# DataConvX13.net
KiCad netlist of a schematic drawn in EAGLE
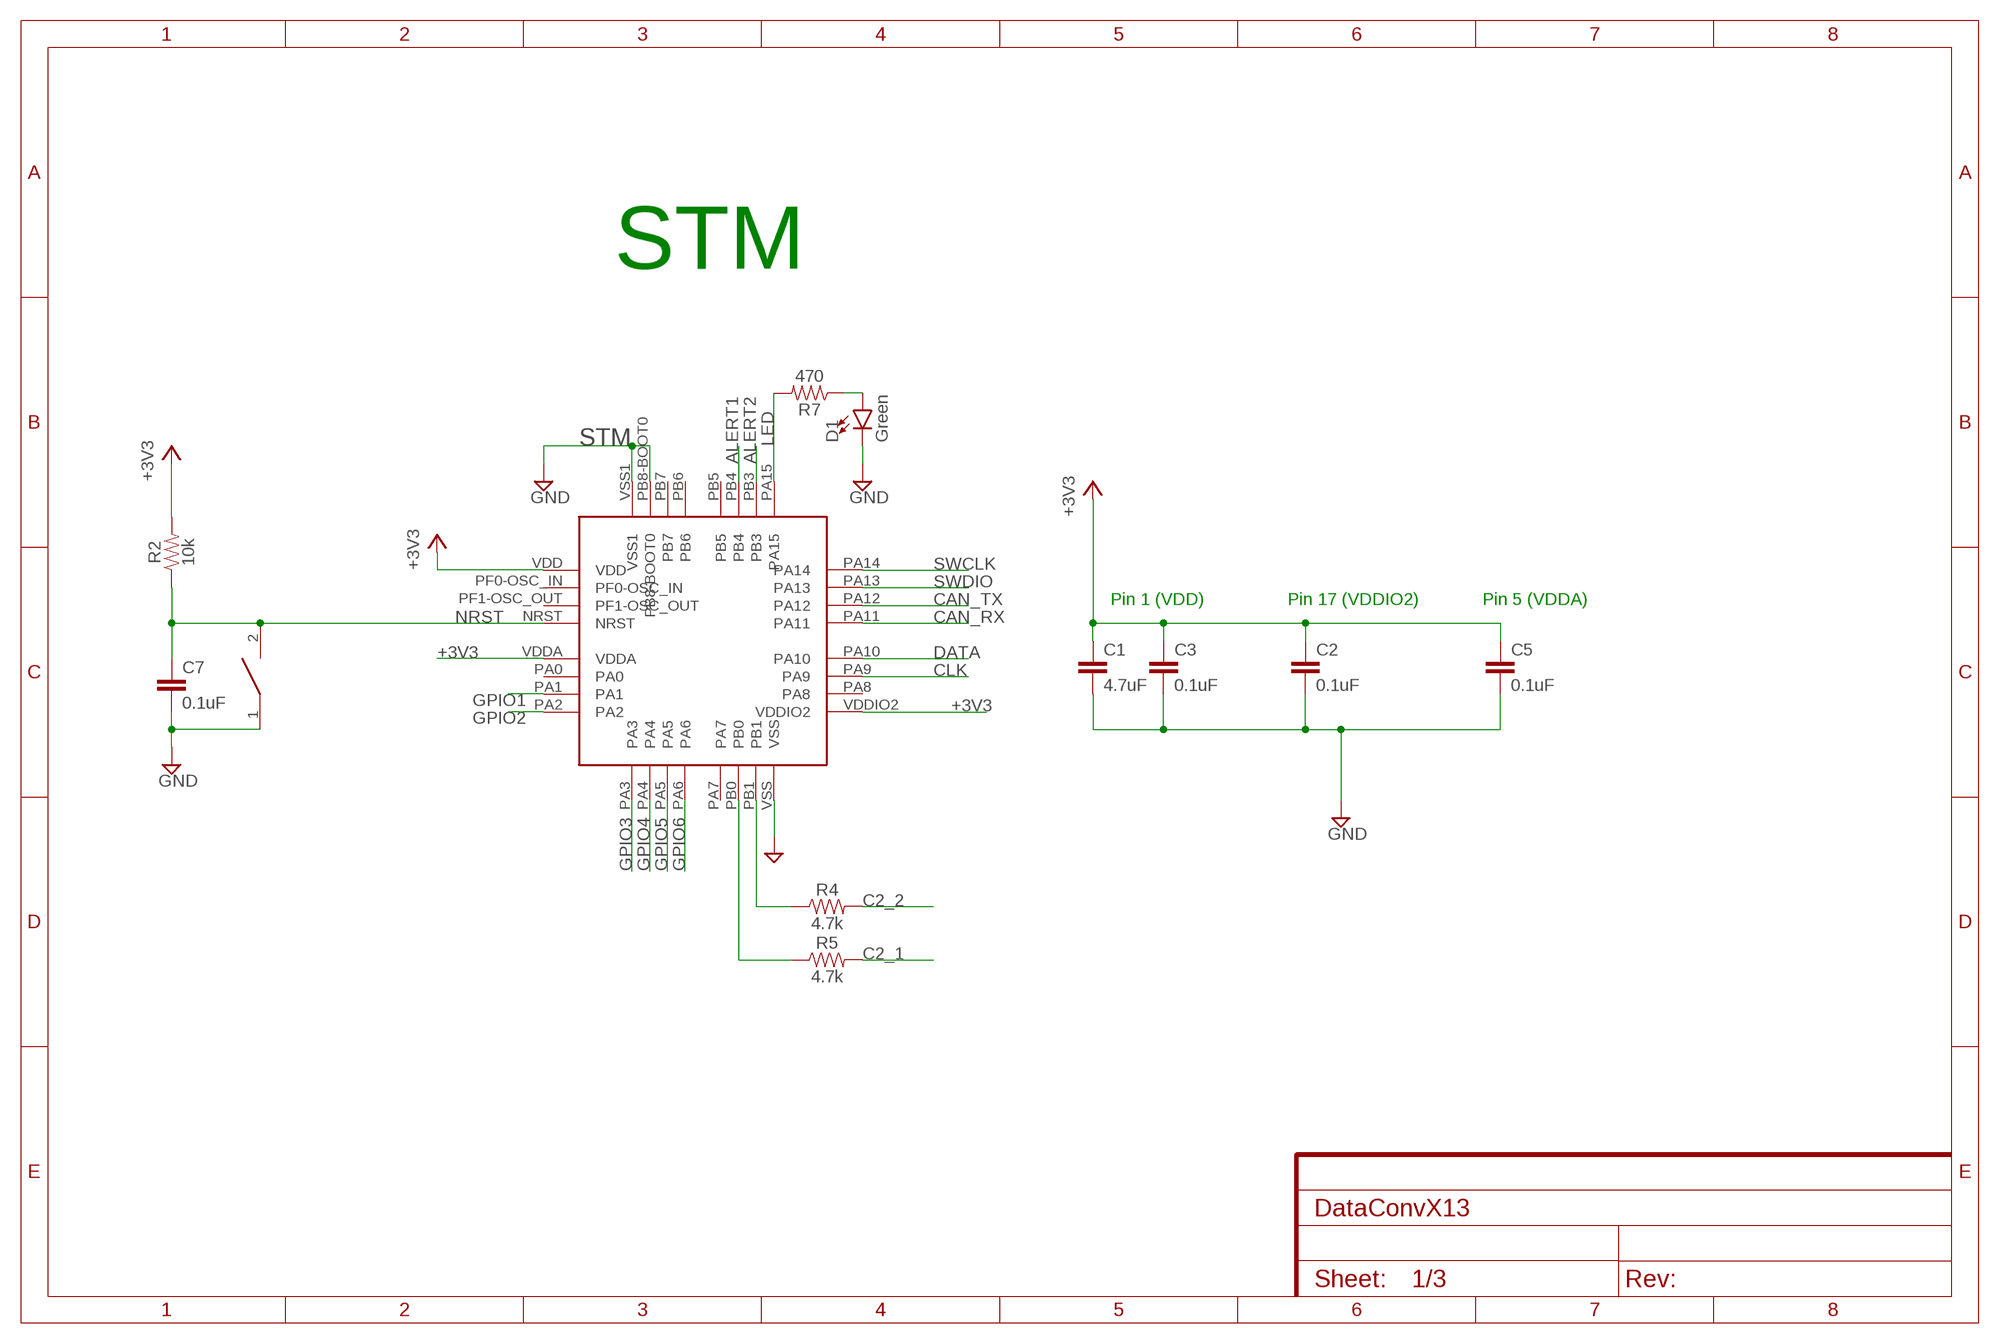
[diagram p0: schematic, sheet 1]
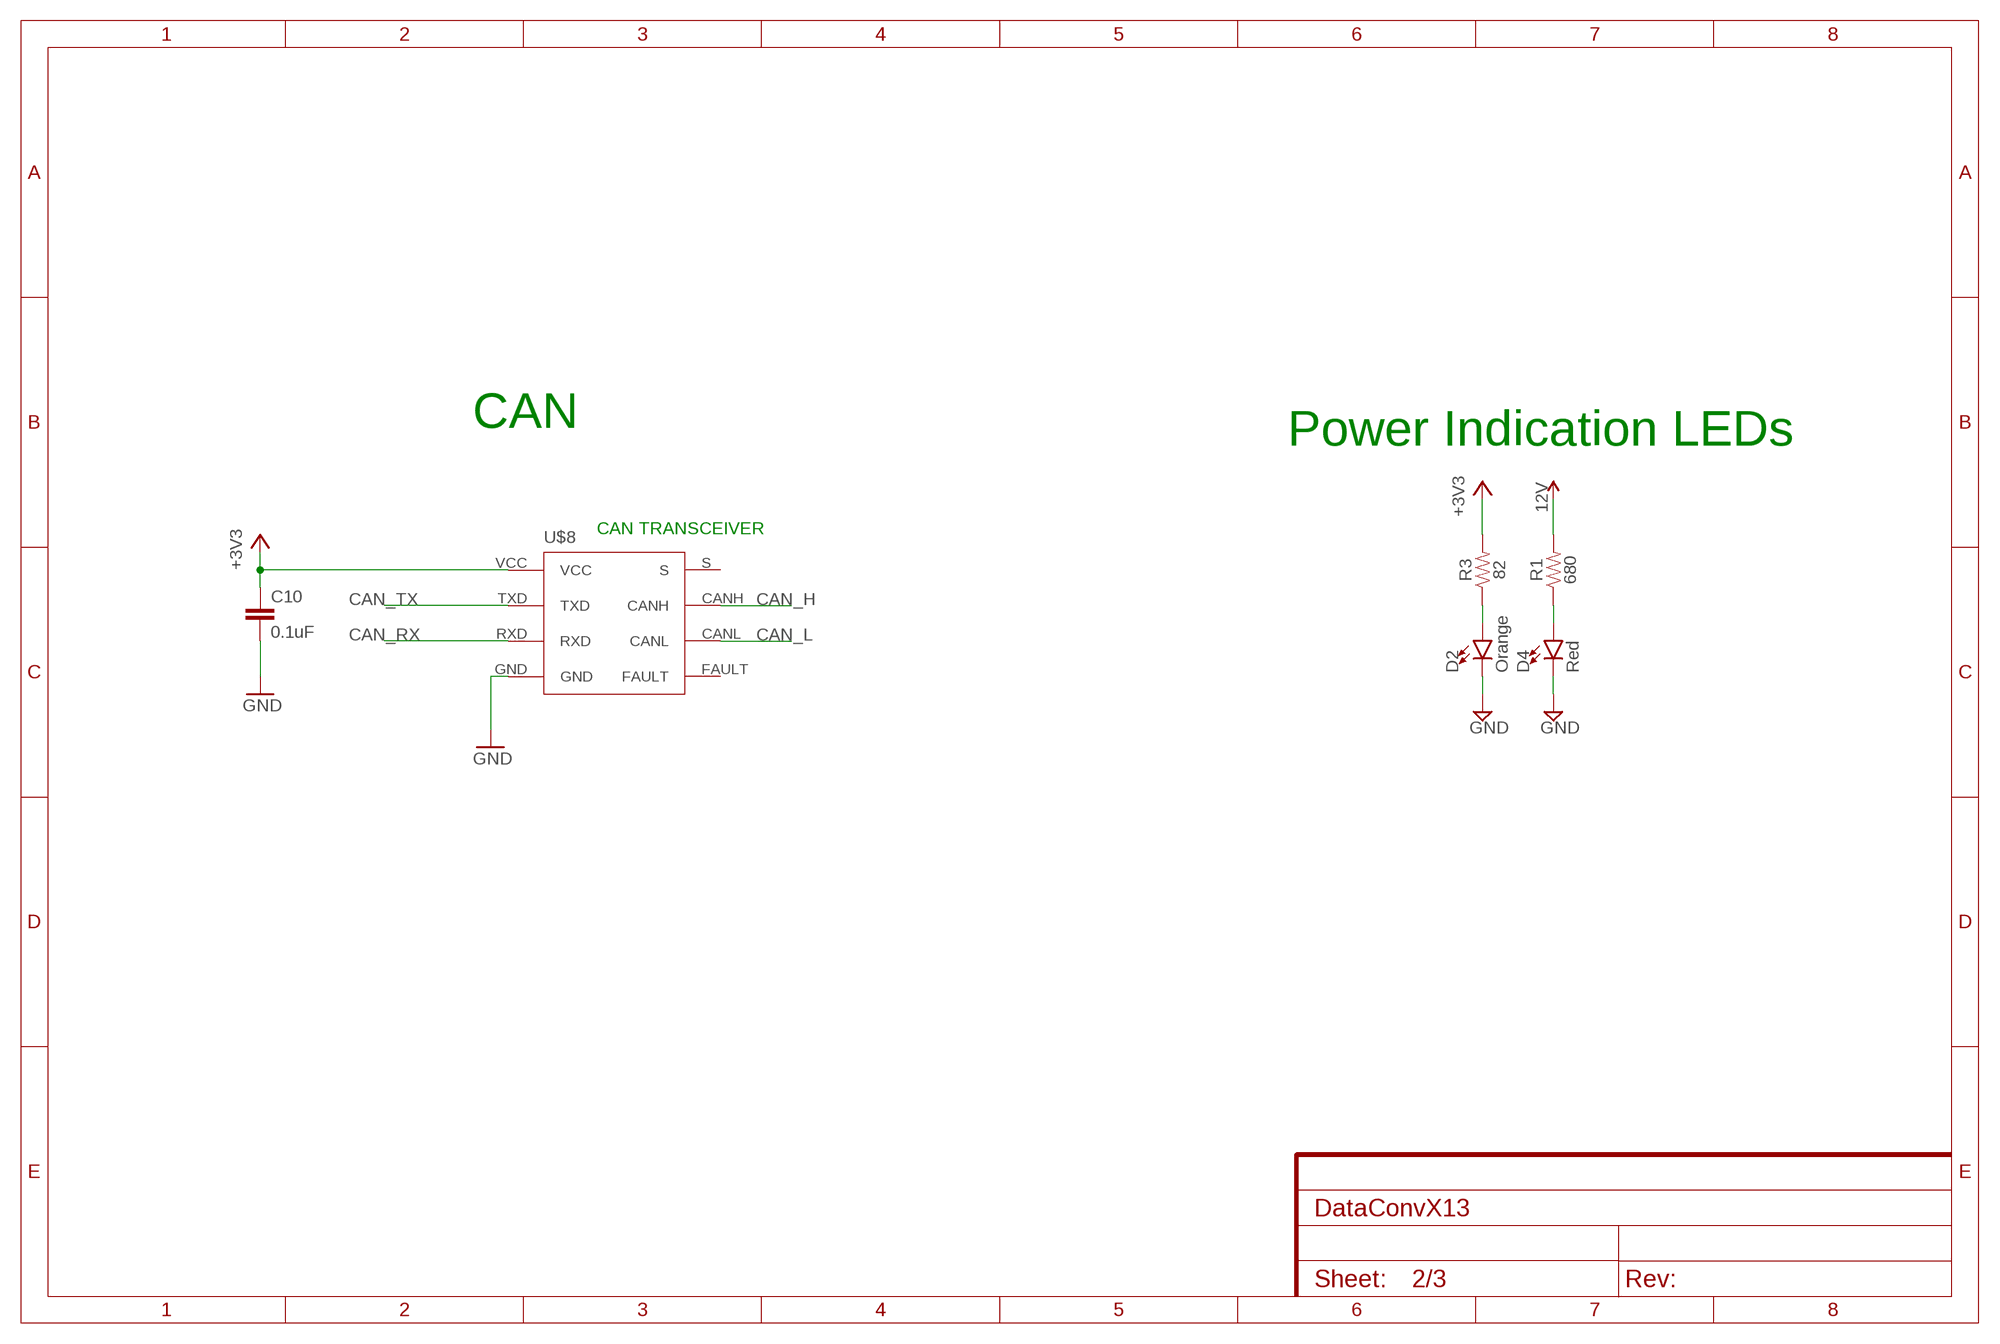
[diagram p1: schematic, sheet 2]
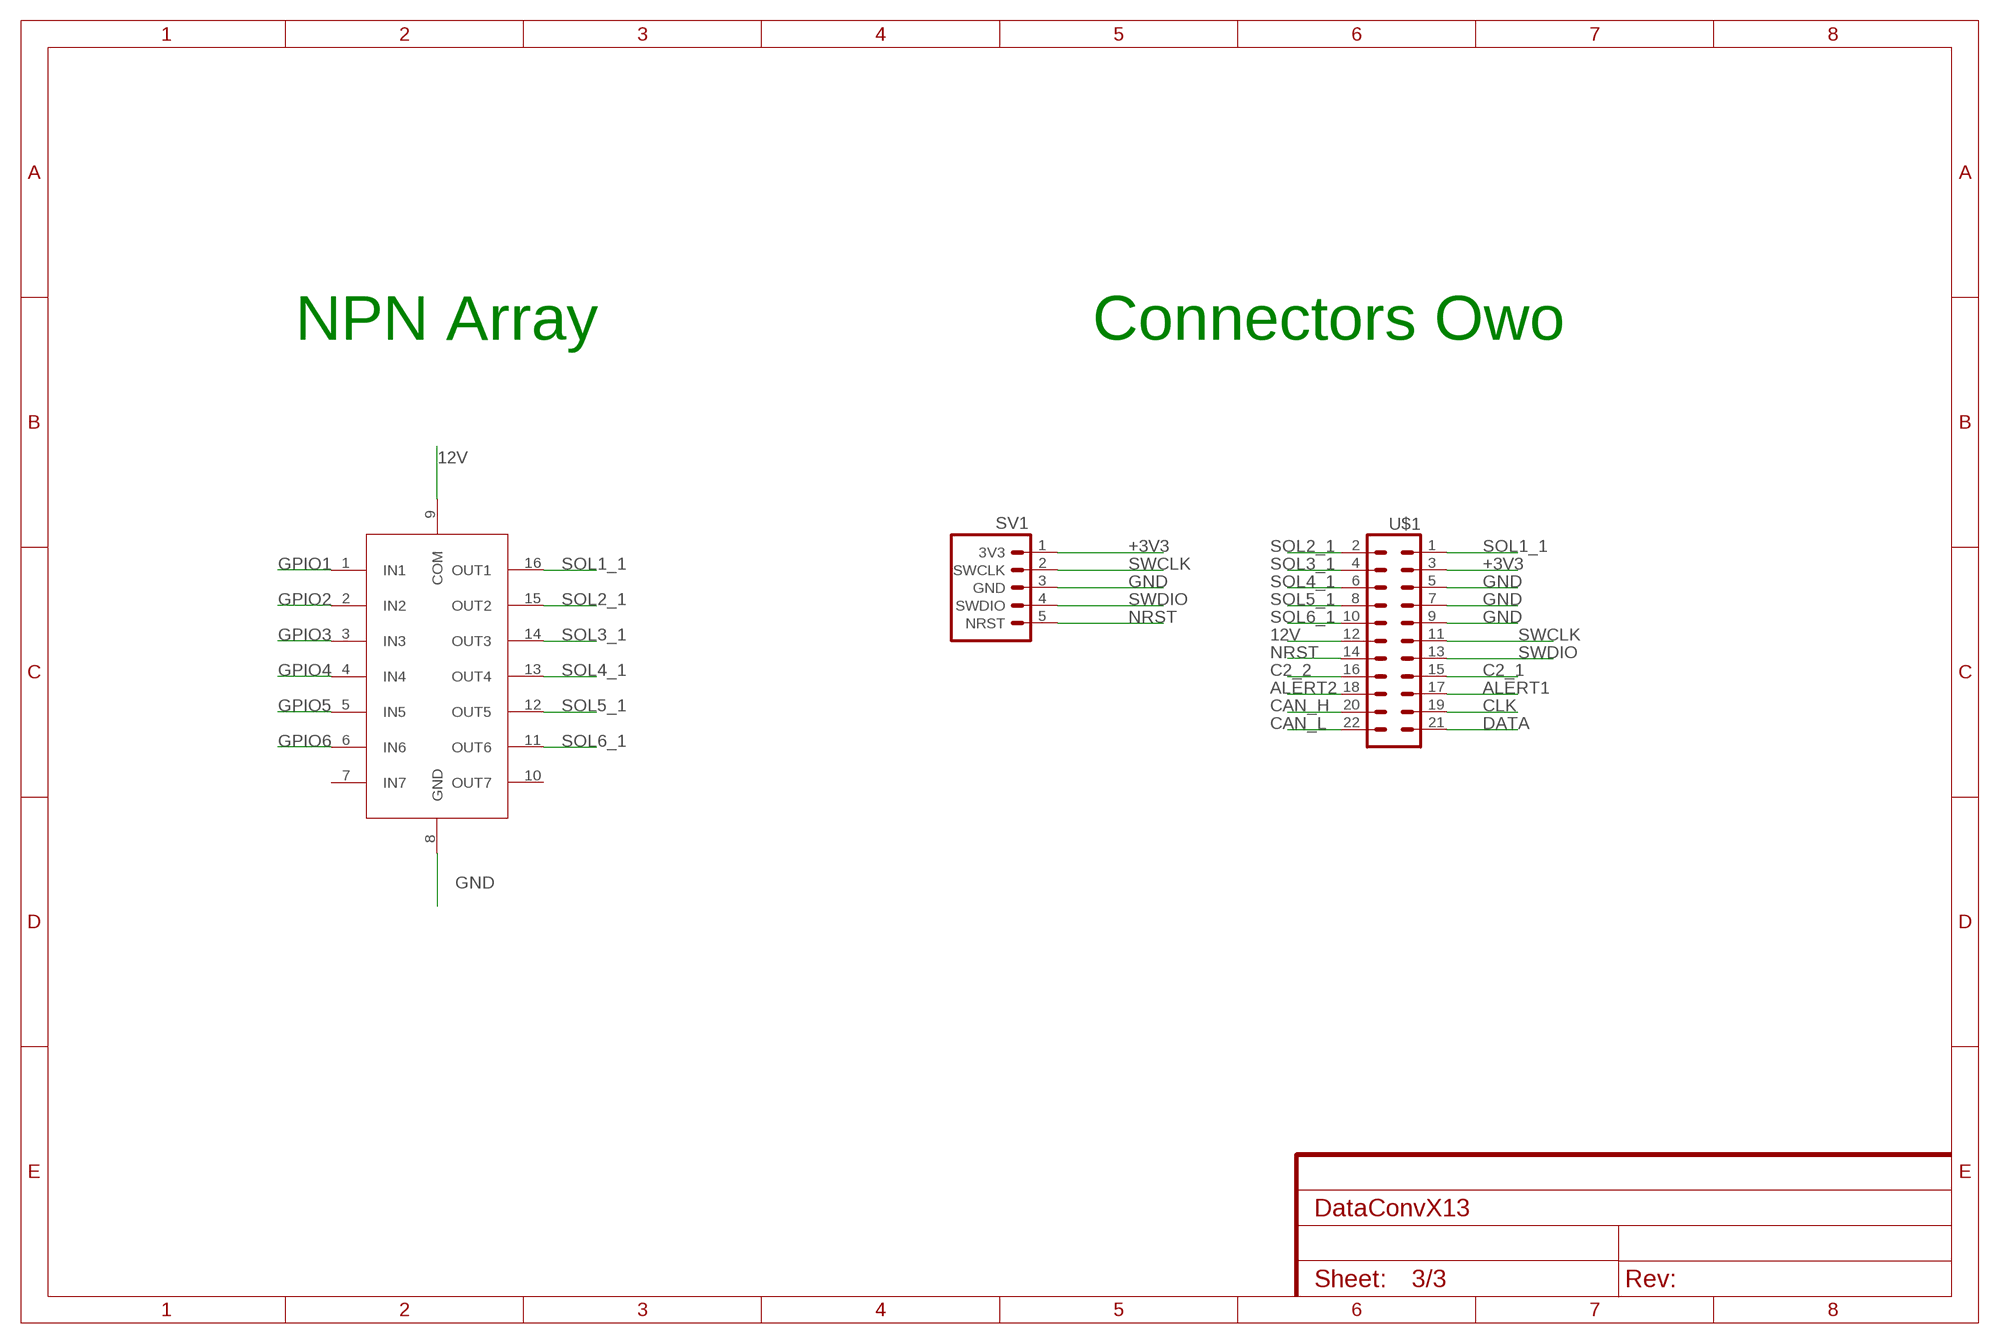
[diagram p2: schematic, sheet 3]

(export (version "E")
  (design (tool "Eeschema 10.0.6"))
  (components
    (comp (ref "C1")
      (value "4.7uF")
      (footprint "eagle-import:0603")
      (libsource (lib "eagle-import") (part "4.7UF0603"))
    )
    (comp (ref "C2")
      (value "0.1uF")
      (footprint "eagle-import:0603")
      (libsource (lib "eagle-import") (part "4.7UF0603"))
    )
    (comp (ref "C3")
      (value "0.1uF")
      (footprint "eagle-import:0603")
      (libsource (lib "eagle-import") (part "4.7UF0603"))
    )
    (comp (ref "C5")
      (value "0.1uF")
      (footprint "eagle-import:0603")
      (libsource (lib "eagle-import") (part "4.7UF0603"))
    )
    (comp (ref "C7")
      (value "0.1uF")
      (footprint "eagle-import:0603")
      (libsource (lib "eagle-import") (part "4.7UF0603"))
    )
    (comp (ref "D1")
      (value "Green")
      (footprint "eagle-import:LED-0603")
      (libsource (lib "eagle-import") (part "LED0603"))
    )
    (comp (ref "R2")
      (value "10k")
      (footprint "eagle-import:0603")
      (libsource (lib "eagle-import") (part "1KOHM-0603-1/10W-1%"))
    )
    (comp (ref "R4")
      (value "4.7k")
      (footprint "eagle-import:0603")
      (libsource (lib "eagle-import") (part "4.7KOHM-0603-1/10W-1%"))
    )
    (comp (ref "R5")
      (value "4.7k")
      (footprint "eagle-import:0603")
      (libsource (lib "eagle-import") (part "4.7KOHM-0603-1/10W-1%"))
    )
    (comp (ref "R7")
      (value "470")
      (footprint "eagle-import:0603")
      (libsource (lib "eagle-import") (part "RESISTOR0603"))
    )
    (comp (ref "RESET")
      (value "DISCRETECOMPONENTS_SWITCH")
      (footprint "eagle-import:DISCRETECOMPONENTS_SW_2512")
      (libsource (lib "eagle-import") (part "DISCRETECOMPONENTS_SWITCH"))
    )
    (comp (ref "STM")
      (value "STM32F042K6T6")
      (footprint "eagle-import:STM32F042K6T6")
      (libsource (lib "eagle-import") (part "STM32F042K6T6"))
    )
    (comp (ref "SV1")
      (value "3V3 -SWCLK-GND-SWDIO- NRST")
      (footprint "eagle-import:1X05")
      (libsource (lib "eagle-import") (part "SWD_CONN"))
    )
    (comp (ref "U$1")
      (value "SOL-TO-BKP")
      (footprint "eagle-import:MMS-111-01-DV")
      (libsource (lib "eagle-import") (part "SOL-TO-BKP"))
    )
    (comp (ref "U1")
      (value "ULN2003V12")
      (footprint "eagle-import:ULN2003V12")
      (fields (field (name "MANUFACTURER") "Diodes Inc."))
      (libsource (lib "eagle-import") (part "ULN2003V12"))
    )
    (comp (ref "C10")
      (value "0.1uF")
      (footprint "eagle-import:0603")
      (libsource (lib "eagle-import") (part "4.7UF0603"))
    )
    (comp (ref "D2")
      (value "Orange")
      (footprint "eagle-import:LED-0603")
      (libsource (lib "eagle-import") (part "LED0603"))
    )
    (comp (ref "D4")
      (value "Red")
      (footprint "eagle-import:LED-0603")
      (libsource (lib "eagle-import") (part "LED0603"))
    )
    (comp (ref "R1")
      (value "680")
      (footprint "eagle-import:0603")
      (libsource (lib "eagle-import") (part "680OHM-0603-1/10W-5%"))
    )
    (comp (ref "R3")
      (value "82")
      (footprint "eagle-import:0603")
      (libsource (lib "eagle-import") (part "82OHM-0603-1/10W-1%"))
    )
    (comp (ref "U$8")
      (value "TCAN337D")
      (footprint "eagle-import:TCAN337D")
      (libsource (lib "eagle-import") (part "TCAN337D"))
    )
  )
  (nets
    (net (code "1") (name "+3V3") (class "Default")
      (node (ref "C1") (pin "1") (pinfunction "1_1") (pintype "passive"))
      (node (ref "C10") (pin "1") (pinfunction "1_1") (pintype "passive"))
      (node (ref "C2") (pin "1") (pinfunction "1_1") (pintype "passive"))
      (node (ref "C3") (pin "1") (pinfunction "1_1") (pintype "passive"))
      (node (ref "C5") (pin "1") (pinfunction "1_1") (pintype "passive"))
      (node (ref "R2") (pin "2") (pinfunction "2_2") (pintype "passive"))
      (node (ref "R3") (pin "2") (pinfunction "2_2") (pintype "passive"))
      (node (ref "STM") (pin "VDD") (pinfunction "VDD_VDD") (pintype "bidirectional"))
      (node (ref "STM") (pin "VDDA") (pinfunction "VDDA_VDDA") (pintype "bidirectional"))
      (node (ref "STM") (pin "VDDIO2") (pinfunction "VDDIO2_VDDIO2") (pintype "bidirectional"))
      (node (ref "SV1") (pin "1") (pinfunction "3V3_1") (pintype "power_in"))
      (node (ref "U$1") (pin "3") (pinfunction "3_3") (pintype "passive"))
      (node (ref "U$8") (pin "VCC") (pinfunction "VCC_VCC") (pintype "bidirectional"))
    )
    (net (code "2") (name "12V") (class "Default")
      (node (ref "R1") (pin "2") (pinfunction "2_2") (pintype "passive"))
      (node (ref "U$1") (pin "12") (pinfunction "12_12") (pintype "passive"))
      (node (ref "U1") (pin "9") (pinfunction "COM_9") (pintype "bidirectional"))
    )
    (net (code "3") (name "ALERT1") (class "Default")
      (node (ref "STM") (pin "PB4") (pinfunction "PB4_PB4") (pintype "bidirectional"))
      (node (ref "U$1") (pin "17") (pinfunction "17_17") (pintype "passive"))
    )
    (net (code "4") (name "ALERT2") (class "Default")
      (node (ref "STM") (pin "PB3") (pinfunction "PB3_PB3") (pintype "bidirectional"))
      (node (ref "U$1") (pin "18") (pinfunction "18_18") (pintype "passive"))
    )
    (net (code "5") (name "C2_1") (class "Default")
      (node (ref "R5") (pin "2") (pinfunction "2_2") (pintype "passive"))
      (node (ref "U$1") (pin "15") (pinfunction "15_15") (pintype "passive"))
    )
    (net (code "6") (name "C2_2") (class "Default")
      (node (ref "R4") (pin "2") (pinfunction "2_2") (pintype "passive"))
      (node (ref "U$1") (pin "16") (pinfunction "16_16") (pintype "passive"))
    )
    (net (code "7") (name "CAN_H") (class "Default")
      (node (ref "U$1") (pin "20") (pinfunction "20_20") (pintype "passive"))
      (node (ref "U$8") (pin "CANH") (pinfunction "CANH_CANH") (pintype "bidirectional"))
    )
    (net (code "8") (name "CAN_L") (class "Default")
      (node (ref "U$1") (pin "22") (pinfunction "22_22") (pintype "passive"))
      (node (ref "U$8") (pin "CANL") (pinfunction "CANL_CANL") (pintype "bidirectional"))
    )
    (net (code "9") (name "CAN_RX") (class "Default")
      (node (ref "STM") (pin "PA11") (pinfunction "PA11_PA11") (pintype "bidirectional"))
      (node (ref "U$8") (pin "RXD") (pinfunction "RXD_RXD") (pintype "bidirectional"))
    )
    (net (code "10") (name "CAN_TX") (class "Default")
      (node (ref "STM") (pin "PA12") (pinfunction "PA12_PA12") (pintype "bidirectional"))
      (node (ref "U$8") (pin "TXD") (pinfunction "TXD_TXD") (pintype "bidirectional"))
    )
    (net (code "11") (name "CLK") (class "Default")
      (node (ref "STM") (pin "PA9") (pinfunction "PA9_PA9") (pintype "bidirectional"))
      (node (ref "U$1") (pin "19") (pinfunction "19_19") (pintype "passive"))
    )
    (net (code "12") (name "DATA") (class "Default")
      (node (ref "STM") (pin "PA10") (pinfunction "PA10_PA10") (pintype "bidirectional"))
      (node (ref "U$1") (pin "21") (pinfunction "21_21") (pintype "passive"))
    )
    (net (code "13") (name "GND") (class "Default")
      (node (ref "C1") (pin "2") (pinfunction "2_2") (pintype "passive"))
      (node (ref "C10") (pin "2") (pinfunction "2_2") (pintype "passive"))
      (node (ref "C2") (pin "2") (pinfunction "2_2") (pintype "passive"))
      (node (ref "C3") (pin "2") (pinfunction "2_2") (pintype "passive"))
      (node (ref "C5") (pin "2") (pinfunction "2_2") (pintype "passive"))
      (node (ref "C7") (pin "2") (pinfunction "2_2") (pintype "passive"))
      (node (ref "D1") (pin "C") (pinfunction "C_C") (pintype "passive"))
      (node (ref "D2") (pin "C") (pinfunction "C_C") (pintype "passive"))
      (node (ref "D4") (pin "C") (pinfunction "C_C") (pintype "passive"))
      (node (ref "RESET") (pin "1") (pinfunction "P$1_1") (pintype "bidirectional"))
      (node (ref "STM") (pin "PB8-BOOT0") (pinfunction "PB8-BOOT0_PB8-BOOT0") (pintype "bidirectional"))
      (node (ref "STM") (pin "VSS") (pinfunction "VSS_VSS") (pintype "bidirectional"))
      (node (ref "STM") (pin "VSS1") (pinfunction "VSS1_VSS1") (pintype "bidirectional"))
      (node (ref "SV1") (pin "3") (pinfunction "GND_3") (pintype "power_in"))
      (node (ref "U$1") (pin "5") (pinfunction "5_5") (pintype "passive"))
      (node (ref "U$1") (pin "7") (pinfunction "7_7") (pintype "passive"))
      (node (ref "U$1") (pin "9") (pinfunction "9_9") (pintype "passive"))
      (node (ref "U$8") (pin "GND") (pinfunction "GND_GND") (pintype "bidirectional"))
      (node (ref "U1") (pin "8") (pinfunction "GND_8") (pintype "bidirectional"))
    )
    (net (code "14") (name "GPIO1") (class "Default")
      (node (ref "STM") (pin "PA1") (pinfunction "PA1_PA1") (pintype "bidirectional"))
      (node (ref "U1") (pin "1") (pinfunction "IN1_1") (pintype "bidirectional"))
    )
    (net (code "15") (name "GPIO2") (class "Default")
      (node (ref "STM") (pin "PA2") (pinfunction "PA2_PA2") (pintype "bidirectional"))
      (node (ref "U1") (pin "2") (pinfunction "IN2_2") (pintype "bidirectional"))
    )
    (net (code "16") (name "GPIO3") (class "Default")
      (node (ref "STM") (pin "PA3") (pinfunction "PA3_PA3") (pintype "bidirectional"))
      (node (ref "U1") (pin "3") (pinfunction "IN3_3") (pintype "bidirectional"))
    )
    (net (code "17") (name "GPIO4") (class "Default")
      (node (ref "STM") (pin "PA4") (pinfunction "PA4_PA4") (pintype "bidirectional"))
      (node (ref "U1") (pin "4") (pinfunction "IN4_4") (pintype "bidirectional"))
    )
    (net (code "18") (name "GPIO5") (class "Default")
      (node (ref "STM") (pin "PA5") (pinfunction "PA5_PA5") (pintype "bidirectional"))
      (node (ref "U1") (pin "5") (pinfunction "IN5_5") (pintype "bidirectional"))
    )
    (net (code "19") (name "GPIO6") (class "Default")
      (node (ref "STM") (pin "PA6") (pinfunction "PA6_PA6") (pintype "bidirectional"))
      (node (ref "U1") (pin "6") (pinfunction "IN6_6") (pintype "bidirectional"))
    )
    (net (code "20") (name "LED") (class "Default")
      (node (ref "R7") (pin "2") (pinfunction "2_2") (pintype "passive"))
      (node (ref "STM") (pin "PA15") (pinfunction "PA15_PA15") (pintype "bidirectional"))
    )
    (net (code "21") (name "NRST") (class "Default")
      (node (ref "C7") (pin "1") (pinfunction "1_1") (pintype "passive"))
      (node (ref "R2") (pin "1") (pinfunction "1_1") (pintype "passive"))
      (node (ref "RESET") (pin "2") (pinfunction "P$2_2") (pintype "bidirectional"))
      (node (ref "STM") (pin "NRST") (pinfunction "NRST_NRST") (pintype "bidirectional"))
      (node (ref "SV1") (pin "5") (pinfunction "NRST_5") (pintype "open_collector"))
      (node (ref "U$1") (pin "14") (pinfunction "14_14") (pintype "passive"))
    )
    (net (code "22") (name "Net-(D1-PadA)") (class "Default")
      (node (ref "D1") (pin "A") (pinfunction "A_A") (pintype "passive"))
      (node (ref "R7") (pin "1") (pinfunction "1_1") (pintype "passive"))
    )
    (net (code "23") (name "Net-(D2-PadA)") (class "Default")
      (node (ref "D2") (pin "A") (pinfunction "A_A") (pintype "passive"))
      (node (ref "R3") (pin "1") (pinfunction "1_1") (pintype "passive"))
    )
    (net (code "24") (name "Net-(D4-PadA)") (class "Default")
      (node (ref "D4") (pin "A") (pinfunction "A_A") (pintype "passive"))
      (node (ref "R1") (pin "1") (pinfunction "1_1") (pintype "passive"))
    )
    (net (code "25") (name "Net-(R4-Pad1)") (class "Default")
      (node (ref "R4") (pin "1") (pinfunction "1_1") (pintype "passive"))
      (node (ref "STM") (pin "PB1") (pinfunction "PB1_PB1") (pintype "bidirectional"))
    )
    (net (code "26") (name "Net-(R5-Pad1)") (class "Default")
      (node (ref "R5") (pin "1") (pinfunction "1_1") (pintype "passive"))
      (node (ref "STM") (pin "PB0") (pinfunction "PB0_PB0") (pintype "bidirectional"))
    )
    (net (code "27") (name "SOL1_1") (class "Default")
      (node (ref "U$1") (pin "1") (pinfunction "1_1") (pintype "passive"))
      (node (ref "U1") (pin "16") (pinfunction "OUT1_16") (pintype "bidirectional"))
    )
    (net (code "28") (name "SOL2_1") (class "Default")
      (node (ref "U$1") (pin "2") (pinfunction "2_2") (pintype "passive"))
      (node (ref "U1") (pin "15") (pinfunction "OUT2_15") (pintype "bidirectional"))
    )
    (net (code "29") (name "SOL3_1") (class "Default")
      (node (ref "U$1") (pin "4") (pinfunction "4_4") (pintype "passive"))
      (node (ref "U1") (pin "14") (pinfunction "OUT3_14") (pintype "bidirectional"))
    )
    (net (code "30") (name "SOL4_1") (class "Default")
      (node (ref "U$1") (pin "6") (pinfunction "6_6") (pintype "passive"))
      (node (ref "U1") (pin "13") (pinfunction "OUT4_13") (pintype "bidirectional"))
    )
    (net (code "31") (name "SOL5_1") (class "Default")
      (node (ref "U$1") (pin "8") (pinfunction "8_8") (pintype "passive"))
      (node (ref "U1") (pin "12") (pinfunction "OUT5_12") (pintype "bidirectional"))
    )
    (net (code "32") (name "SOL6_1") (class "Default")
      (node (ref "U$1") (pin "10") (pinfunction "10_10") (pintype "passive"))
      (node (ref "U1") (pin "11") (pinfunction "OUT6_11") (pintype "bidirectional"))
    )
    (net (code "33") (name "SWCLK") (class "Default")
      (node (ref "STM") (pin "PA14") (pinfunction "PA14_PA14") (pintype "bidirectional"))
      (node (ref "SV1") (pin "2") (pinfunction "SWCLK_2") (pintype "input"))
      (node (ref "U$1") (pin "11") (pinfunction "11_11") (pintype "passive"))
    )
    (net (code "34") (name "SWDIO") (class "Default")
      (node (ref "STM") (pin "PA13") (pinfunction "PA13_PA13") (pintype "bidirectional"))
      (node (ref "SV1") (pin "4") (pinfunction "SWDIO_4") (pintype "bidirectional"))
      (node (ref "U$1") (pin "13") (pinfunction "13_13") (pintype "passive"))
    )
    (net (code "35") (name "unconnected-(STM-PadPA0)") (class "Default")
      (node (ref "STM") (pin "PA0") (pinfunction "PA0_PA0") (pintype "bidirectional"))
    )
    (net (code "36") (name "unconnected-(STM-PadPA7)") (class "Default")
      (node (ref "STM") (pin "PA7") (pinfunction "PA7_PA7") (pintype "bidirectional"))
    )
    (net (code "37") (name "unconnected-(STM-PadPA8)") (class "Default")
      (node (ref "STM") (pin "PA8") (pinfunction "PA8_PA8") (pintype "bidirectional"))
    )
    (net (code "38") (name "unconnected-(STM-PadPB5)") (class "Default")
      (node (ref "STM") (pin "PB5") (pinfunction "PB5_PB5") (pintype "bidirectional"))
    )
    (net (code "39") (name "unconnected-(STM-PadPB6)") (class "Default")
      (node (ref "STM") (pin "PB6") (pinfunction "PB6_PB6") (pintype "bidirectional"))
    )
    (net (code "40") (name "unconnected-(STM-PadPB7)") (class "Default")
      (node (ref "STM") (pin "PB7") (pinfunction "PB7_PB7") (pintype "bidirectional"))
    )
    (net (code "41") (name "unconnected-(STM-PadPF0-OSC_IN)") (class "Default")
      (node (ref "STM") (pin "PF0-OSC_IN") (pinfunction "PF0-OSC_IN_PF0-OSC_IN") (pintype "bidirectional"))
    )
    (net (code "42") (name "unconnected-(STM-PadPF1-OSC_OUT)") (class "Default")
      (node (ref "STM") (pin "PF1-OSC_OUT") (pinfunction "PF1-OSC_OUT_PF1-OSC_OUT") (pintype "bidirectional"))
    )
    (net (code "43") (name "unconnected-(U$8-PadFAULT)") (class "Default")
      (node (ref "U$8") (pin "FAULT") (pinfunction "FAULT_FAULT") (pintype "bidirectional"))
    )
    (net (code "44") (name "unconnected-(U$8-PadS)") (class "Default")
      (node (ref "U$8") (pin "S") (pinfunction "S_S") (pintype "bidirectional"))
    )
    (net (code "45") (name "unconnected-(U1-IN7-Pad7)") (class "Default")
      (node (ref "U1") (pin "7") (pinfunction "IN7_7") (pintype "bidirectional"))
    )
    (net (code "46") (name "unconnected-(U1-OUT7-Pad10)") (class "Default")
      (node (ref "U1") (pin "10") (pinfunction "OUT7_10") (pintype "bidirectional"))
    )
  )
)
